# 1_BTB.net
KiCad netlist of a schematic drawn in Altium Designer
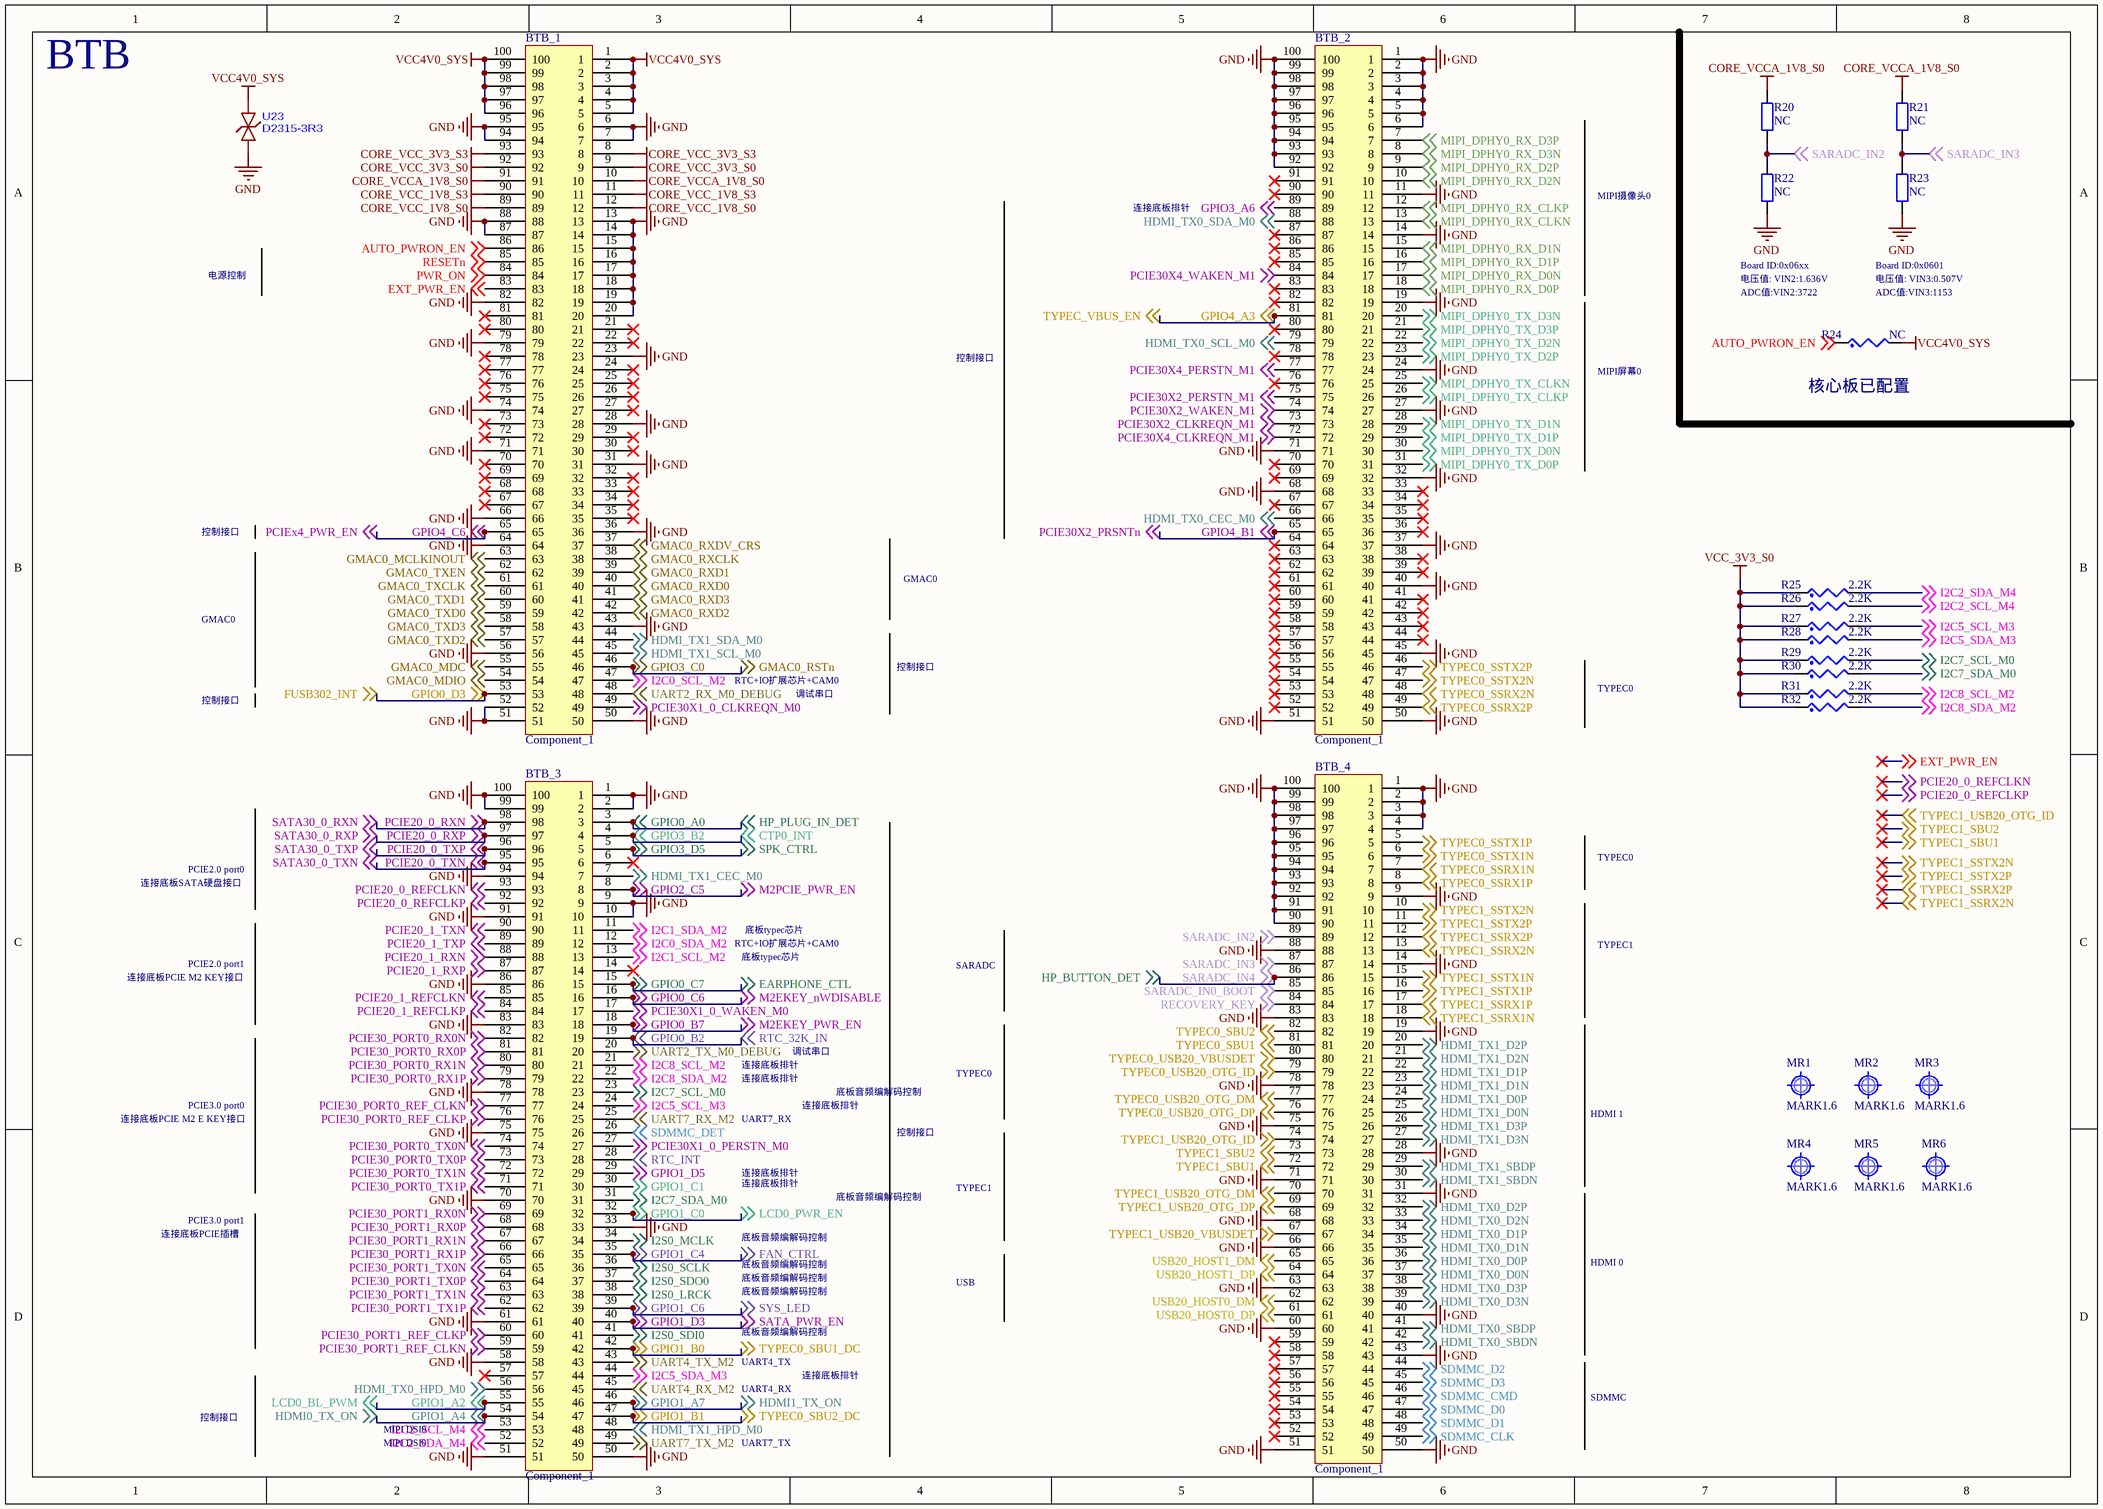
[diagram p0: 1.BTB.SchDoc]

(export (version "E")
  (design (tool "Eeschema 10.0.6"))
  (components
    (comp (ref "BTB_1")
      (value "Component_1")
      (footprint "0.PCB1:F_100PIN")
      (libsource (lib "RK3588底板") (part "Component_1"))
    )
    (comp (ref "BTB_2")
      (value "Component_1")
      (footprint "0.PCB1:F_100PIN")
      (libsource (lib "RK3588底板") (part "Component_1"))
    )
    (comp (ref "BTB_3")
      (value "Component_1")
      (footprint "0.PCB1:F_100PIN")
      (libsource (lib "RK3588底板") (part "Component_1"))
    )
    (comp (ref "BTB_4")
      (value "Component_1")
      (footprint "0.PCB1:F_100PIN")
      (libsource (lib "RK3588底板") (part "Component_1"))
    )
    (comp (ref "MR1")
      (value "MARK1.6")
      (footprint "0.PCB1:Mark 1")
      (description "光学定位点")
      (libsource (lib "RK3588底板") (part "MARK"))
    )
    (comp (ref "MR2")
      (value "MARK1.6")
      (footprint "0.PCB1:Mark 1")
      (description "光学定位点")
      (libsource (lib "RK3588底板") (part "MARK"))
    )
    (comp (ref "MR3")
      (value "MARK1.6")
      (footprint "0.PCB1:Mark 1")
      (description "光学定位点")
      (libsource (lib "RK3588底板") (part "MARK"))
    )
    (comp (ref "MR4")
      (value "MARK1.6")
      (footprint "0.PCB1:Mark 1")
      (description "光学定位点")
      (libsource (lib "RK3588底板") (part "MARK"))
    )
    (comp (ref "MR5")
      (value "MARK1.6")
      (footprint "0.PCB1:Mark 1")
      (description "光学定位点")
      (libsource (lib "RK3588底板") (part "MARK"))
    )
    (comp (ref "MR6")
      (value "MARK1.6")
      (footprint "0.PCB1:Mark 1")
      (description "光学定位点")
      (libsource (lib "RK3588底板") (part "MARK"))
    )
    (comp (ref "R20")
      (value "NC")
      (footprint "0.PCB1:R0402_L")
      (description "贴片电阻")
      (libsource (lib "RK3588底板") (part "R"))
    )
    (comp (ref "R21")
      (value "NC")
      (footprint "0.PCB1:R0402_L")
      (description "贴片电阻")
      (libsource (lib "RK3588底板") (part "R"))
    )
    (comp (ref "R22")
      (value "NC")
      (footprint "0.PCB1:R0402_L")
      (description "贴片电阻")
      (libsource (lib "RK3588底板") (part "R"))
    )
    (comp (ref "R23")
      (value "NC")
      (footprint "0.PCB1:R0402_L")
      (description "贴片电阻")
      (libsource (lib "RK3588底板") (part "R"))
    )
    (comp (ref "R24") (value "NC") (footprint "0.PCB1:R0402") (libsource (lib "RK3588底板") (part "RES")))
    (comp (ref "R25") (value "2.2K") (footprint "0.PCB1:R0402") (libsource (lib "RK3588底板") (part "RES")))
    (comp (ref "R26") (value "2.2K") (footprint "0.PCB1:R0402") (libsource (lib "RK3588底板") (part "RES")))
    (comp (ref "R27") (value "2.2K") (footprint "0.PCB1:R0402") (libsource (lib "RK3588底板") (part "RES")))
    (comp (ref "R28") (value "2.2K") (footprint "0.PCB1:R0402") (libsource (lib "RK3588底板") (part "RES")))
    (comp (ref "R29") (value "2.2K") (footprint "0.PCB1:R0402") (libsource (lib "RK3588底板") (part "RES")))
    (comp (ref "R30") (value "2.2K") (footprint "0.PCB1:R0402") (libsource (lib "RK3588底板") (part "RES")))
    (comp (ref "R31") (value "2.2K") (footprint "0.PCB1:R0402") (libsource (lib "RK3588底板") (part "RES")))
    (comp (ref "R32") (value "2.2K") (footprint "0.PCB1:R0402") (libsource (lib "RK3588底板") (part "RES")))
    (comp (ref "U23")
      (value "D2315-3R3")
      (footprint "0.PCB1:DFN1006-2L-BI")
      (libsource (lib "RK3588底板") (part "D2315-3R3"))
    )
  )
  (nets
    (net (code "1") (name "AUTO_PWRON_EN") (class "Default")
      (node (ref "BTB_1") (pin "86") (pinfunction "86_86") (pintype "passive"))
      (node (ref "R24") (pin "1") (pinfunction "1_1") (pintype "passive"))
    )
    (net (code "2") (name "CORE_VCCA_1V8_S0") (class "Default")
      (node (ref "BTB_1") (pin "10") (pinfunction "10_10") (pintype "passive"))
      (node (ref "BTB_1") (pin "91") (pinfunction "91_91") (pintype "passive"))
      (node (ref "R20") (pin "2") (pinfunction "2_2") (pintype "passive"))
      (node (ref "R21") (pin "2") (pinfunction "2_2") (pintype "passive"))
    )
    (net (code "3") (name "CORE_VCC_1V8_S0") (class "Default")
      (node (ref "BTB_1") (pin "12") (pinfunction "12_12") (pintype "passive"))
      (node (ref "BTB_1") (pin "89") (pinfunction "89_89") (pintype "passive"))
    )
    (net (code "4") (name "CORE_VCC_1V8_S3") (class "Default")
      (node (ref "BTB_1") (pin "11") (pinfunction "11_11") (pintype "passive"))
      (node (ref "BTB_1") (pin "90") (pinfunction "90_90") (pintype "passive"))
    )
    (net (code "5") (name "CORE_VCC_3V3_S0") (class "Default")
      (node (ref "BTB_1") (pin "9") (pinfunction "9_9") (pintype "passive"))
      (node (ref "BTB_1") (pin "92") (pinfunction "92_92") (pintype "passive"))
    )
    (net (code "6") (name "CORE_VCC_3V3_S3") (class "Default")
      (node (ref "BTB_1") (pin "8") (pinfunction "8_8") (pintype "passive"))
      (node (ref "BTB_1") (pin "93") (pinfunction "93_93") (pintype "passive"))
    )
    (net (code "7") (name "CTP0_INT") (class "Default")
      (node (ref "BTB_3") (pin "4") (pinfunction "4_4") (pintype "passive"))
    )
    (net (code "8") (name "EARPHONE_CTL") (class "Default")
      (node (ref "BTB_3") (pin "15") (pinfunction "15_15") (pintype "passive"))
    )
    (net (code "9") (name "EXT_PWR_EN") (class "Default")
      (node (ref "BTB_1") (pin "83") (pinfunction "83_83") (pintype "passive"))
    )
    (net (code "10") (name "FAN_CTRL") (class "Default")
      (node (ref "BTB_3") (pin "35") (pinfunction "35_35") (pintype "passive"))
    )
    (net (code "11") (name "FUSB302_INT") (class "Default")
      (node (ref "BTB_1") (pin "53") (pinfunction "53_53") (pintype "passive"))
    )
    (net (code "12") (name "GMAC0_MCLKINOUT") (class "Default")
      (node (ref "BTB_1") (pin "63") (pinfunction "63_63") (pintype "passive"))
    )
    (net (code "13") (name "GMAC0_MDC") (class "Default")
      (node (ref "BTB_1") (pin "55") (pinfunction "55_55") (pintype "passive"))
    )
    (net (code "14") (name "GMAC0_MDIO") (class "Default")
      (node (ref "BTB_1") (pin "54") (pinfunction "54_54") (pintype "passive"))
    )
    (net (code "15") (name "GMAC0_RSTn") (class "Default")
      (node (ref "BTB_1") (pin "46") (pinfunction "46_46") (pintype "passive"))
    )
    (net (code "16") (name "GMAC0_RXCLK") (class "Default")
      (node (ref "BTB_1") (pin "38") (pinfunction "38_38") (pintype "passive"))
    )
    (net (code "17") (name "GMAC0_RXD0") (class "Default")
      (node (ref "BTB_1") (pin "40") (pinfunction "40_40") (pintype "passive"))
    )
    (net (code "18") (name "GMAC0_RXD1") (class "Default")
      (node (ref "BTB_1") (pin "39") (pinfunction "39_39") (pintype "passive"))
    )
    (net (code "19") (name "GMAC0_RXD2") (class "Default")
      (node (ref "BTB_1") (pin "42") (pinfunction "42_42") (pintype "passive"))
    )
    (net (code "20") (name "GMAC0_RXD3") (class "Default")
      (node (ref "BTB_1") (pin "41") (pinfunction "41_41") (pintype "passive"))
    )
    (net (code "21") (name "GMAC0_RXDV_CRS") (class "Default")
      (node (ref "BTB_1") (pin "37") (pinfunction "37_37") (pintype "passive"))
    )
    (net (code "22") (name "GMAC0_TXCLK") (class "Default")
      (node (ref "BTB_1") (pin "61") (pinfunction "61_61") (pintype "passive"))
    )
    (net (code "23") (name "GMAC0_TXD0") (class "Default")
      (node (ref "BTB_1") (pin "59") (pinfunction "59_59") (pintype "passive"))
    )
    (net (code "24") (name "GMAC0_TXD1") (class "Default")
      (node (ref "BTB_1") (pin "60") (pinfunction "60_60") (pintype "passive"))
    )
    (net (code "25") (name "GMAC0_TXD2") (class "Default")
      (node (ref "BTB_1") (pin "57") (pinfunction "57_57") (pintype "passive"))
    )
    (net (code "26") (name "GMAC0_TXD3") (class "Default")
      (node (ref "BTB_1") (pin "58") (pinfunction "58_58") (pintype "passive"))
    )
    (net (code "27") (name "GMAC0_TXEN") (class "Default")
      (node (ref "BTB_1") (pin "62") (pinfunction "62_62") (pintype "passive"))
    )
    (net (code "28") (name "GND") (class "Default")
      (node (ref "BTB_1") (pin "13") (pinfunction "13_13") (pintype "passive"))
      (node (ref "BTB_1") (pin "14") (pinfunction "14_14") (pintype "passive"))
      (node (ref "BTB_1") (pin "15") (pinfunction "15_15") (pintype "passive"))
      (node (ref "BTB_1") (pin "16") (pinfunction "16_16") (pintype "passive"))
      (node (ref "BTB_1") (pin "17") (pinfunction "17_17") (pintype "passive"))
      (node (ref "BTB_1") (pin "18") (pinfunction "18_18") (pintype "passive"))
      (node (ref "BTB_1") (pin "19") (pinfunction "19_19") (pintype "passive"))
      (node (ref "BTB_1") (pin "20") (pinfunction "20_20") (pintype "passive"))
      (node (ref "BTB_1") (pin "23") (pinfunction "23_23") (pintype "passive"))
      (node (ref "BTB_1") (pin "28") (pinfunction "28_28") (pintype "passive"))
      (node (ref "BTB_1") (pin "31") (pinfunction "31_31") (pintype "passive"))
      (node (ref "BTB_1") (pin "36") (pinfunction "36_36") (pintype "passive"))
      (node (ref "BTB_1") (pin "43") (pinfunction "43_43") (pintype "passive"))
      (node (ref "BTB_1") (pin "50") (pinfunction "50_50") (pintype "passive"))
      (node (ref "BTB_1") (pin "51") (pinfunction "51_51") (pintype "passive"))
      (node (ref "BTB_1") (pin "52") (pinfunction "52_52") (pintype "passive"))
      (node (ref "BTB_1") (pin "56") (pinfunction "56_56") (pintype "passive"))
      (node (ref "BTB_1") (pin "6") (pinfunction "6_6") (pintype "passive"))
      (node (ref "BTB_1") (pin "64") (pinfunction "64_64") (pintype "passive"))
      (node (ref "BTB_1") (pin "66") (pinfunction "66_66") (pintype "passive"))
      (node (ref "BTB_1") (pin "7") (pinfunction "7_7") (pintype "passive"))
      (node (ref "BTB_1") (pin "71") (pinfunction "71_71") (pintype "passive"))
      (node (ref "BTB_1") (pin "74") (pinfunction "74_74") (pintype "passive"))
      (node (ref "BTB_1") (pin "79") (pinfunction "79_79") (pintype "passive"))
      (node (ref "BTB_1") (pin "82") (pinfunction "82_82") (pintype "passive"))
      (node (ref "BTB_1") (pin "87") (pinfunction "87_87") (pintype "passive"))
      (node (ref "BTB_1") (pin "88") (pinfunction "88_88") (pintype "passive"))
      (node (ref "BTB_1") (pin "94") (pinfunction "94_94") (pintype "passive"))
      (node (ref "BTB_1") (pin "95") (pinfunction "95_95") (pintype "passive"))
      (node (ref "BTB_2") (pin "1") (pinfunction "1_1") (pintype "passive"))
      (node (ref "BTB_2") (pin "100") (pinfunction "100_100") (pintype "passive"))
      (node (ref "BTB_2") (pin "11") (pinfunction "11_11") (pintype "passive"))
      (node (ref "BTB_2") (pin "14") (pinfunction "14_14") (pintype "passive"))
      (node (ref "BTB_2") (pin "19") (pinfunction "19_19") (pintype "passive"))
      (node (ref "BTB_2") (pin "2") (pinfunction "2_2") (pintype "passive"))
      (node (ref "BTB_2") (pin "24") (pinfunction "24_24") (pintype "passive"))
      (node (ref "BTB_2") (pin "27") (pinfunction "27_27") (pintype "passive"))
      (node (ref "BTB_2") (pin "3") (pinfunction "3_3") (pintype "passive"))
      (node (ref "BTB_2") (pin "32") (pinfunction "32_32") (pintype "passive"))
      (node (ref "BTB_2") (pin "37") (pinfunction "37_37") (pintype "passive"))
      (node (ref "BTB_2") (pin "4") (pinfunction "4_4") (pintype "passive"))
      (node (ref "BTB_2") (pin "40") (pinfunction "40_40") (pintype "passive"))
      (node (ref "BTB_2") (pin "45") (pinfunction "45_45") (pintype "passive"))
      (node (ref "BTB_2") (pin "5") (pinfunction "5_5") (pintype "passive"))
      (node (ref "BTB_2") (pin "50") (pinfunction "50_50") (pintype "passive"))
      (node (ref "BTB_2") (pin "51") (pinfunction "51_51") (pintype "passive"))
      (node (ref "BTB_2") (pin "6") (pinfunction "6_6") (pintype "passive"))
      (node (ref "BTB_2") (pin "68") (pinfunction "68_68") (pintype "passive"))
      (node (ref "BTB_2") (pin "71") (pinfunction "71_71") (pintype "passive"))
      (node (ref "BTB_2") (pin "92") (pinfunction "92_92") (pintype "passive"))
      (node (ref "BTB_2") (pin "93") (pinfunction "93_93") (pintype "passive"))
      (node (ref "BTB_2") (pin "94") (pinfunction "94_94") (pintype "passive"))
      (node (ref "BTB_2") (pin "95") (pinfunction "95_95") (pintype "passive"))
      (node (ref "BTB_2") (pin "96") (pinfunction "96_96") (pintype "passive"))
      (node (ref "BTB_2") (pin "97") (pinfunction "97_97") (pintype "passive"))
      (node (ref "BTB_2") (pin "98") (pinfunction "98_98") (pintype "passive"))
      (node (ref "BTB_2") (pin "99") (pinfunction "99_99") (pintype "passive"))
      (node (ref "BTB_3") (pin "1") (pinfunction "1_1") (pintype "passive"))
      (node (ref "BTB_3") (pin "10") (pinfunction "10_10") (pintype "passive"))
      (node (ref "BTB_3") (pin "100") (pinfunction "100_100") (pintype "passive"))
      (node (ref "BTB_3") (pin "2") (pinfunction "2_2") (pintype "passive"))
      (node (ref "BTB_3") (pin "33") (pinfunction "33_33") (pintype "passive"))
      (node (ref "BTB_3") (pin "50") (pinfunction "50_50") (pintype "passive"))
      (node (ref "BTB_3") (pin "51") (pinfunction "51_51") (pintype "passive"))
      (node (ref "BTB_3") (pin "58") (pinfunction "58_58") (pintype "passive"))
      (node (ref "BTB_3") (pin "61") (pinfunction "61_61") (pintype "passive"))
      (node (ref "BTB_3") (pin "70") (pinfunction "70_70") (pintype "passive"))
      (node (ref "BTB_3") (pin "75") (pinfunction "75_75") (pintype "passive"))
      (node (ref "BTB_3") (pin "78") (pinfunction "78_78") (pintype "passive"))
      (node (ref "BTB_3") (pin "83") (pinfunction "83_83") (pintype "passive"))
      (node (ref "BTB_3") (pin "86") (pinfunction "86_86") (pintype "passive"))
      (node (ref "BTB_3") (pin "9") (pinfunction "9_9") (pintype "passive"))
      (node (ref "BTB_3") (pin "91") (pinfunction "91_91") (pintype "passive"))
      (node (ref "BTB_3") (pin "94") (pinfunction "94_94") (pintype "passive"))
      (node (ref "BTB_3") (pin "99") (pinfunction "99_99") (pintype "passive"))
      (node (ref "BTB_4") (pin "1") (pinfunction "1_1") (pintype "passive"))
      (node (ref "BTB_4") (pin "100") (pinfunction "100_100") (pintype "passive"))
      (node (ref "BTB_4") (pin "14") (pinfunction "14_14") (pintype "passive"))
      (node (ref "BTB_4") (pin "19") (pinfunction "19_19") (pintype "passive"))
      (node (ref "BTB_4") (pin "2") (pinfunction "2_2") (pintype "passive"))
      (node (ref "BTB_4") (pin "28") (pinfunction "28_28") (pintype "passive"))
      (node (ref "BTB_4") (pin "3") (pinfunction "3_3") (pintype "passive"))
      (node (ref "BTB_4") (pin "31") (pinfunction "31_31") (pintype "passive"))
      (node (ref "BTB_4") (pin "4") (pinfunction "4_4") (pintype "passive"))
      (node (ref "BTB_4") (pin "40") (pinfunction "40_40") (pintype "passive"))
      (node (ref "BTB_4") (pin "43") (pinfunction "43_43") (pintype "passive"))
      (node (ref "BTB_4") (pin "50") (pinfunction "50_50") (pintype "passive"))
      (node (ref "BTB_4") (pin "51") (pinfunction "51_51") (pintype "passive"))
      (node (ref "BTB_4") (pin "60") (pinfunction "60_60") (pintype "passive"))
      (node (ref "BTB_4") (pin "63") (pinfunction "63_63") (pintype "passive"))
      (node (ref "BTB_4") (pin "66") (pinfunction "66_66") (pintype "passive"))
      (node (ref "BTB_4") (pin "68") (pinfunction "68_68") (pintype "passive"))
      (node (ref "BTB_4") (pin "71") (pinfunction "71_71") (pintype "passive"))
      (node (ref "BTB_4") (pin "75") (pinfunction "75_75") (pintype "passive"))
      (node (ref "BTB_4") (pin "78") (pinfunction "78_78") (pintype "passive"))
      (node (ref "BTB_4") (pin "83") (pinfunction "83_83") (pintype "passive"))
      (node (ref "BTB_4") (pin "88") (pinfunction "88_88") (pintype "passive"))
      (node (ref "BTB_4") (pin "9") (pinfunction "9_9") (pintype "passive"))
      (node (ref "BTB_4") (pin "90") (pinfunction "90_90") (pintype "passive"))
      (node (ref "BTB_4") (pin "91") (pinfunction "91_91") (pintype "passive"))
      (node (ref "BTB_4") (pin "92") (pinfunction "92_92") (pintype "passive"))
      (node (ref "BTB_4") (pin "93") (pinfunction "93_93") (pintype "passive"))
      (node (ref "BTB_4") (pin "94") (pinfunction "94_94") (pintype "passive"))
      (node (ref "BTB_4") (pin "95") (pinfunction "95_95") (pintype "passive"))
      (node (ref "BTB_4") (pin "96") (pinfunction "96_96") (pintype "passive"))
      (node (ref "BTB_4") (pin "97") (pinfunction "97_97") (pintype "passive"))
      (node (ref "BTB_4") (pin "98") (pinfunction "98_98") (pintype "passive"))
      (node (ref "BTB_4") (pin "99") (pinfunction "99_99") (pintype "passive"))
      (node (ref "R22") (pin "1") (pinfunction "1_1") (pintype "passive"))
      (node (ref "R23") (pin "1") (pinfunction "1_1") (pintype "passive"))
      (node (ref "U23") (pin "1") (pinfunction "1_1") (pintype "passive"))
    )
    (net (code "29") (name "GPIO0_A0") (class "Default")
      (node (ref "BTB_3") (pin "3") (pinfunction "3_3") (pintype "passive"))
    )
    (net (code "30") (name "GPIO0_B2") (class "Default")
      (node (ref "BTB_3") (pin "19") (pinfunction "19_19") (pintype "passive"))
    )
    (net (code "31") (name "GPIO0_B7") (class "Default")
      (node (ref "BTB_3") (pin "18") (pinfunction "18_18") (pintype "passive"))
    )
    (net (code "32") (name "GPIO0_C6") (class "Default")
      (node (ref "BTB_3") (pin "16") (pinfunction "16_16") (pintype "passive"))
    )
    (net (code "33") (name "GPIO1_A2") (class "Default")
      (node (ref "BTB_3") (pin "55") (pinfunction "55_55") (pintype "passive"))
    )
    (net (code "34") (name "GPIO1_A4") (class "Default")
      (node (ref "BTB_3") (pin "54") (pinfunction "54_54") (pintype "passive"))
    )
    (net (code "35") (name "GPIO1_A7") (class "Default")
      (node (ref "BTB_3") (pin "46") (pinfunction "46_46") (pintype "passive"))
    )
    (net (code "36") (name "GPIO1_B0") (class "Default")
      (node (ref "BTB_3") (pin "42") (pinfunction "42_42") (pintype "passive"))
    )
    (net (code "37") (name "GPIO1_B1") (class "Default")
      (node (ref "BTB_3") (pin "47") (pinfunction "47_47") (pintype "passive"))
    )
    (net (code "38") (name "GPIO1_C0") (class "Default")
      (node (ref "BTB_3") (pin "32") (pinfunction "32_32") (pintype "passive"))
    )
    (net (code "39") (name "GPIO1_C1") (class "Default")
      (node (ref "BTB_3") (pin "30") (pinfunction "30_30") (pintype "passive"))
    )
    (net (code "40") (name "GPIO1_C6") (class "Default")
      (node (ref "BTB_3") (pin "39") (pinfunction "39_39") (pintype "passive"))
    )
    (net (code "41") (name "GPIO1_D3") (class "Default")
      (node (ref "BTB_3") (pin "40") (pinfunction "40_40") (pintype "passive"))
    )
    (net (code "42") (name "GPIO1_D5") (class "Default")
      (node (ref "BTB_3") (pin "29") (pinfunction "29_29") (pintype "passive"))
    )
    (net (code "43") (name "GPIO2_C5") (class "Default")
      (node (ref "BTB_3") (pin "8") (pinfunction "8_8") (pintype "passive"))
    )
    (net (code "44") (name "GPIO3_A6") (class "Default")
      (node (ref "BTB_2") (pin "89") (pinfunction "89_89") (pintype "passive"))
    )
    (net (code "45") (name "GPIO3_D5") (class "Default")
      (node (ref "BTB_3") (pin "5") (pinfunction "5_5") (pintype "passive"))
    )
    (net (code "46") (name "GPIO4_A3") (class "Default")
      (node (ref "BTB_2") (pin "81") (pinfunction "81_81") (pintype "passive"))
    )
    (net (code "47") (name "GPIO4_B1") (class "Default")
      (node (ref "BTB_2") (pin "65") (pinfunction "65_65") (pintype "passive"))
    )
    (net (code "48") (name "GPIO4_C6") (class "Default")
      (node (ref "BTB_1") (pin "65") (pinfunction "65_65") (pintype "passive"))
    )
    (net (code "49") (name "HDMI_TX0_CEC_M0") (class "Default")
      (node (ref "BTB_2") (pin "66") (pinfunction "66_66") (pintype "passive"))
    )
    (net (code "50") (name "HDMI_TX0_D0N") (class "Default")
      (node (ref "BTB_4") (pin "37") (pinfunction "37_37") (pintype "passive"))
    )
    (net (code "51") (name "HDMI_TX0_D0P") (class "Default")
      (node (ref "BTB_4") (pin "36") (pinfunction "36_36") (pintype "passive"))
    )
    (net (code "52") (name "HDMI_TX0_D1N") (class "Default")
      (node (ref "BTB_4") (pin "35") (pinfunction "35_35") (pintype "passive"))
    )
    (net (code "53") (name "HDMI_TX0_D1P") (class "Default")
      (node (ref "BTB_4") (pin "34") (pinfunction "34_34") (pintype "passive"))
    )
    (net (code "54") (name "HDMI_TX0_D2N") (class "Default")
      (node (ref "BTB_4") (pin "33") (pinfunction "33_33") (pintype "passive"))
    )
    (net (code "55") (name "HDMI_TX0_D2P") (class "Default")
      (node (ref "BTB_4") (pin "32") (pinfunction "32_32") (pintype "passive"))
    )
    (net (code "56") (name "HDMI_TX0_D3N") (class "Default")
      (node (ref "BTB_4") (pin "39") (pinfunction "39_39") (pintype "passive"))
    )
    (net (code "57") (name "HDMI_TX0_D3P") (class "Default")
      (node (ref "BTB_4") (pin "38") (pinfunction "38_38") (pintype "passive"))
    )
    (net (code "58") (name "HDMI_TX0_HPD_M0") (class "Default")
      (node (ref "BTB_3") (pin "56") (pinfunction "56_56") (pintype "passive"))
    )
    (net (code "59") (name "HDMI_TX0_SBDN") (class "Default")
      (node (ref "BTB_4") (pin "42") (pinfunction "42_42") (pintype "passive"))
    )
    (net (code "60") (name "HDMI_TX0_SBDP") (class "Default")
      (node (ref "BTB_4") (pin "41") (pinfunction "41_41") (pintype "passive"))
    )
    (net (code "61") (name "HDMI_TX0_SCL_M0") (class "Default")
      (node (ref "BTB_2") (pin "79") (pinfunction "79_79") (pintype "passive"))
    )
    (net (code "62") (name "HDMI_TX0_SDA_M0") (class "Default")
      (node (ref "BTB_2") (pin "88") (pinfunction "88_88") (pintype "passive"))
    )
    (net (code "63") (name "HDMI_TX1_CEC_M0") (class "Default")
      (node (ref "BTB_3") (pin "7") (pinfunction "7_7") (pintype "passive"))
    )
    (net (code "64") (name "HDMI_TX1_D0N") (class "Default")
      (node (ref "BTB_4") (pin "25") (pinfunction "25_25") (pintype "passive"))
    )
    (net (code "65") (name "HDMI_TX1_D0P") (class "Default")
      (node (ref "BTB_4") (pin "24") (pinfunction "24_24") (pintype "passive"))
    )
    (net (code "66") (name "HDMI_TX1_D1N") (class "Default")
      (node (ref "BTB_4") (pin "23") (pinfunction "23_23") (pintype "passive"))
    )
    (net (code "67") (name "HDMI_TX1_D1P") (class "Default")
      (node (ref "BTB_4") (pin "22") (pinfunction "22_22") (pintype "passive"))
    )
    (net (code "68") (name "HDMI_TX1_D2N") (class "Default")
      (node (ref "BTB_4") (pin "21") (pinfunction "21_21") (pintype "passive"))
    )
    (net (code "69") (name "HDMI_TX1_D2P") (class "Default")
      (node (ref "BTB_4") (pin "20") (pinfunction "20_20") (pintype "passive"))
    )
    (net (code "70") (name "HDMI_TX1_D3N") (class "Default")
      (node (ref "BTB_4") (pin "27") (pinfunction "27_27") (pintype "passive"))
    )
    (net (code "71") (name "HDMI_TX1_D3P") (class "Default")
      (node (ref "BTB_4") (pin "26") (pinfunction "26_26") (pintype "passive"))
    )
    (net (code "72") (name "HDMI_TX1_HPD_M0") (class "Default")
      (node (ref "BTB_3") (pin "48") (pinfunction "48_48") (pintype "passive"))
    )
    (net (code "73") (name "HDMI_TX1_SBDN") (class "Default")
      (node (ref "BTB_4") (pin "30") (pinfunction "30_30") (pintype "passive"))
    )
    (net (code "74") (name "HDMI_TX1_SBDP") (class "Default")
      (node (ref "BTB_4") (pin "29") (pinfunction "29_29") (pintype "passive"))
    )
    (net (code "75") (name "HDMI_TX1_SCL_M0") (class "Default")
      (node (ref "BTB_1") (pin "45") (pinfunction "45_45") (pintype "passive"))
    )
    (net (code "76") (name "HDMI_TX1_SDA_M0") (class "Default")
      (node (ref "BTB_1") (pin "44") (pinfunction "44_44") (pintype "passive"))
    )
    (net (code "77") (name "HP_BUTTON_DET") (class "Default")
      (node (ref "BTB_4") (pin "86") (pinfunction "86_86") (pintype "passive"))
    )
    (net (code "78") (name "I2C0_SCL_M2") (class "Default")
      (node (ref "BTB_1") (pin "47") (pinfunction "47_47") (pintype "passive"))
    )
    (net (code "79") (name "I2C0_SDA_M2") (class "Default")
      (node (ref "BTB_3") (pin "12") (pinfunction "12_12") (pintype "passive"))
    )
    (net (code "80") (name "I2C1_SCL_M2") (class "Default")
      (node (ref "BTB_3") (pin "13") (pinfunction "13_13") (pintype "passive"))
    )
    (net (code "81") (name "I2C1_SDA_M2") (class "Default")
      (node (ref "BTB_3") (pin "11") (pinfunction "11_11") (pintype "passive"))
    )
    (net (code "82") (name "I2C2_SCL_M4") (class "Default")
      (node (ref "BTB_3") (pin "53") (pinfunction "53_53") (pintype "passive"))
      (node (ref "R26") (pin "2") (pinfunction "2_2") (pintype "passive"))
    )
    (net (code "83") (name "I2C2_SDA_M4") (class "Default")
      (node (ref "BTB_3") (pin "52") (pinfunction "52_52") (pintype "passive"))
      (node (ref "R25") (pin "2") (pinfunction "2_2") (pintype "passive"))
    )
    (net (code "84") (name "I2C5_SCL_M3") (class "Default")
      (node (ref "BTB_3") (pin "24") (pinfunction "24_24") (pintype "passive"))
      (node (ref "R27") (pin "2") (pinfunction "2_2") (pintype "passive"))
    )
    (net (code "85") (name "I2C5_SDA_M3") (class "Default")
      (node (ref "BTB_3") (pin "44") (pinfunction "44_44") (pintype "passive"))
      (node (ref "R28") (pin "2") (pinfunction "2_2") (pintype "passive"))
    )
    (net (code "86") (name "I2C7_SCL_M0") (class "Default")
      (node (ref "BTB_3") (pin "23") (pinfunction "23_23") (pintype "passive"))
      (node (ref "R29") (pin "2") (pinfunction "2_2") (pintype "passive"))
    )
    (net (code "87") (name "I2C7_SDA_M0") (class "Default")
      (node (ref "BTB_3") (pin "31") (pinfunction "31_31") (pintype "passive"))
      (node (ref "R30") (pin "2") (pinfunction "2_2") (pintype "passive"))
    )
    (net (code "88") (name "I2C8_SCL_M2") (class "Default")
      (node (ref "BTB_3") (pin "21") (pinfunction "21_21") (pintype "passive"))
      (node (ref "R31") (pin "2") (pinfunction "2_2") (pintype "passive"))
    )
    (net (code "89") (name "I2C8_SDA_M2") (class "Default")
      (node (ref "BTB_3") (pin "22") (pinfunction "22_22") (pintype "passive"))
      (node (ref "R32") (pin "2") (pinfunction "2_2") (pintype "passive"))
    )
    (net (code "90") (name "I2S0_LRCK") (class "Default")
      (node (ref "BTB_3") (pin "38") (pinfunction "38_38") (pintype "passive"))
    )
    (net (code "91") (name "I2S0_MCLK") (class "Default")
      (node (ref "BTB_3") (pin "34") (pinfunction "34_34") (pintype "passive"))
    )
    (net (code "92") (name "I2S0_SCLK") (class "Default")
      (node (ref "BTB_3") (pin "36") (pinfunction "36_36") (pintype "passive"))
    )
    (net (code "93") (name "I2S0_SDI0") (class "Default")
      (node (ref "BTB_3") (pin "41") (pinfunction "41_41") (pintype "passive"))
    )
    (net (code "94") (name "I2S0_SDO0") (class "Default")
      (node (ref "BTB_3") (pin "37") (pinfunction "37_37") (pintype "passive"))
    )
    (net (code "95") (name "MIPI_DPHY0_RX_CLKN") (class "Default")
      (node (ref "BTB_2") (pin "13") (pinfunction "13_13") (pintype "passive"))
    )
    (net (code "96") (name "MIPI_DPHY0_RX_CLKP") (class "Default")
      (node (ref "BTB_2") (pin "12") (pinfunction "12_12") (pintype "passive"))
    )
    (net (code "97") (name "MIPI_DPHY0_RX_D0N") (class "Default")
      (node (ref "BTB_2") (pin "17") (pinfunction "17_17") (pintype "passive"))
    )
    (net (code "98") (name "MIPI_DPHY0_RX_D0P") (class "Default")
      (node (ref "BTB_2") (pin "18") (pinfunction "18_18") (pintype "passive"))
    )
    (net (code "99") (name "MIPI_DPHY0_RX_D1N") (class "Default")
      (node (ref "BTB_2") (pin "15") (pinfunction "15_15") (pintype "passive"))
    )
    (net (code "100") (name "MIPI_DPHY0_RX_D1P") (class "Default")
      (node (ref "BTB_2") (pin "16") (pinfunction "16_16") (pintype "passive"))
    )
    (net (code "101") (name "MIPI_DPHY0_RX_D2N") (class "Default")
      (node (ref "BTB_2") (pin "10") (pinfunction "10_10") (pintype "passive"))
    )
    (net (code "102") (name "MIPI_DPHY0_RX_D2P") (class "Default")
      (node (ref "BTB_2") (pin "9") (pinfunction "9_9") (pintype "passive"))
    )
    (net (code "103") (name "MIPI_DPHY0_RX_D3N") (class "Default")
      (node (ref "BTB_2") (pin "8") (pinfunction "8_8") (pintype "passive"))
    )
    (net (code "104") (name "MIPI_DPHY0_RX_D3P") (class "Default")
      (node (ref "BTB_2") (pin "7") (pinfunction "7_7") (pintype "passive"))
    )
    (net (code "105") (name "MIPI_DPHY0_TX_CLKN") (class "Default")
      (node (ref "BTB_2") (pin "25") (pinfunction "25_25") (pintype "passive"))
    )
    (net (code "106") (name "MIPI_DPHY0_TX_CLKP") (class "Default")
      (node (ref "BTB_2") (pin "26") (pinfunction "26_26") (pintype "passive"))
    )
    (net (code "107") (name "MIPI_DPHY0_TX_D0N") (class "Default")
      (node (ref "BTB_2") (pin "30") (pinfunction "30_30") (pintype "passive"))
    )
    (net (code "108") (name "MIPI_DPHY0_TX_D0P") (class "Default")
      (node (ref "BTB_2") (pin "31") (pinfunction "31_31") (pintype "passive"))
    )
    (net (code "109") (name "MIPI_DPHY0_TX_D1N") (class "Default")
      (node (ref "BTB_2") (pin "28") (pinfunction "28_28") (pintype "passive"))
    )
    (net (code "110") (name "MIPI_DPHY0_TX_D1P") (class "Default")
      (node (ref "BTB_2") (pin "29") (pinfunction "29_29") (pintype "passive"))
    )
    (net (code "111") (name "MIPI_DPHY0_TX_D2N") (class "Default")
      (node (ref "BTB_2") (pin "22") (pinfunction "22_22") (pintype "passive"))
    )
    (net (code "112") (name "MIPI_DPHY0_TX_D2P") (class "Default")
      (node (ref "BTB_2") (pin "23") (pinfunction "23_23") (pintype "passive"))
    )
    (net (code "113") (name "MIPI_DPHY0_TX_D3N") (class "Default")
      (node (ref "BTB_2") (pin "20") (pinfunction "20_20") (pintype "passive"))
    )
    (net (code "114") (name "MIPI_DPHY0_TX_D3P") (class "Default")
      (node (ref "BTB_2") (pin "21") (pinfunction "21_21") (pintype "passive"))
    )
    (net (code "115") (name "PCIE20_0_REFCLKN") (class "Default")
      (node (ref "BTB_3") (pin "93") (pinfunction "93_93") (pintype "passive"))
    )
    (net (code "116") (name "PCIE20_0_REFCLKP") (class "Default")
      (node (ref "BTB_3") (pin "92") (pinfunction "92_92") (pintype "passive"))
    )
    (net (code "117") (name "PCIE20_0_RXN") (class "Default")
      (node (ref "BTB_3") (pin "98") (pinfunction "98_98") (pintype "passive"))
    )
    (net (code "118") (name "PCIE20_0_RXP") (class "Default")
      (node (ref "BTB_3") (pin "97") (pinfunction "97_97") (pintype "passive"))
    )
    (net (code "119") (name "PCIE20_0_TXN") (class "Default")
      (node (ref "BTB_3") (pin "95") (pinfunction "95_95") (pintype "passive"))
    )
    (net (code "120") (name "PCIE20_0_TXP") (class "Default")
      (node (ref "BTB_3") (pin "96") (pinfunction "96_96") (pintype "passive"))
    )
    (net (code "121") (name "PCIE20_1_REFCLKN") (class "Default")
      (node (ref "BTB_3") (pin "85") (pinfunction "85_85") (pintype "passive"))
    )
    (net (code "122") (name "PCIE20_1_REFCLKP") (class "Default")
      (node (ref "BTB_3") (pin "84") (pinfunction "84_84") (pintype "passive"))
    )
    (net (code "123") (name "PCIE20_1_RXN") (class "Default")
      (node (ref "BTB_3") (pin "88") (pinfunction "88_88") (pintype "passive"))
    )
    (net (code "124") (name "PCIE20_1_RXP") (class "Default")
      (node (ref "BTB_3") (pin "87") (pinfunction "87_87") (pintype "passive"))
    )
    (net (code "125") (name "PCIE20_1_TXN") (class "Default")
      (node (ref "BTB_3") (pin "90") (pinfunction "90_90") (pintype "passive"))
    )
    (net (code "126") (name "PCIE20_1_TXP") (class "Default")
      (node (ref "BTB_3") (pin "89") (pinfunction "89_89") (pintype "passive"))
    )
    (net (code "127") (name "PCIE30X1_0_CLKREQN_M0") (class "Default")
      (node (ref "BTB_1") (pin "49") (pinfunction "49_49") (pintype "passive"))
    )
    (net (code "128") (name "PCIE30X1_0_PERSTN_M0") (class "Default")
      (node (ref "BTB_3") (pin "27") (pinfunction "27_27") (pintype "passive"))
    )
    (net (code "129") (name "PCIE30X1_0_WAKEN_M0") (class "Default")
      (node (ref "BTB_3") (pin "17") (pinfunction "17_17") (pintype "passive"))
    )
    (net (code "130") (name "PCIE30X2_CLKREQN_M1") (class "Default")
      (node (ref "BTB_2") (pin "73") (pinfunction "73_73") (pintype "passive"))
    )
    (net (code "131") (name "PCIE30X2_PERSTN_M1") (class "Default")
      (node (ref "BTB_2") (pin "75") (pinfunction "75_75") (pintype "passive"))
    )
    (net (code "132") (name "PCIE30X2_WAKEN_M1") (class "Default")
      (node (ref "BTB_2") (pin "74") (pinfunction "74_74") (pintype "passive"))
    )
    (net (code "133") (name "PCIE30X4_CLKREQN_M1") (class "Default")
      (node (ref "BTB_2") (pin "72") (pinfunction "72_72") (pintype "passive"))
    )
    (net (code "134") (name "PCIE30X4_PERSTN_M1") (class "Default")
      (node (ref "BTB_2") (pin "77") (pinfunction "77_77") (pintype "passive"))
    )
    (net (code "135") (name "PCIE30X4_WAKEN_M1") (class "Default")
      (node (ref "BTB_2") (pin "84") (pinfunction "84_84") (pintype "passive"))
    )
    (net (code "136") (name "PCIE30_PORT0_REF_CLKN") (class "Default")
      (node (ref "BTB_3") (pin "77") (pinfunction "77_77") (pintype "passive"))
    )
    (net (code "137") (name "PCIE30_PORT0_REF_CLKP") (class "Default")
      (node (ref "BTB_3") (pin "76") (pinfunction "76_76") (pintype "passive"))
    )
    (net (code "138") (name "PCIE30_PORT0_RX0N") (class "Default")
      (node (ref "BTB_3") (pin "82") (pinfunction "82_82") (pintype "passive"))
    )
    (net (code "139") (name "PCIE30_PORT0_RX0P") (class "Default")
      (node (ref "BTB_3") (pin "81") (pinfunction "81_81") (pintype "passive"))
    )
    (net (code "140") (name "PCIE30_PORT0_RX1N") (class "Default")
      (node (ref "BTB_3") (pin "80") (pinfunction "80_80") (pintype "passive"))
    )
    (net (code "141") (name "PCIE30_PORT0_RX1P") (class "Default")
      (node (ref "BTB_3") (pin "79") (pinfunction "79_79") (pintype "passive"))
    )
    (net (code "142") (name "PCIE30_PORT0_TX0N") (class "Default")
      (node (ref "BTB_3") (pin "74") (pinfunction "74_74") (pintype "passive"))
    )
    (net (code "143") (name "PCIE30_PORT0_TX0P") (class "Default")
      (node (ref "BTB_3") (pin "73") (pinfunction "73_73") (pintype "passive"))
    )
    (net (code "144") (name "PCIE30_PORT0_TX1N") (class "Default")
      (node (ref "BTB_3") (pin "72") (pinfunction "72_72") (pintype "passive"))
    )
    (net (code "145") (name "PCIE30_PORT0_TX1P") (class "Default")
      (node (ref "BTB_3") (pin "71") (pinfunction "71_71") (pintype "passive"))
    )
    (net (code "146") (name "PCIE30_PORT1_REF_CLKN") (class "Default")
      (node (ref "BTB_3") (pin "59") (pinfunction "59_59") (pintype "passive"))
    )
    (net (code "147") (name "PCIE30_PORT1_REF_CLKP") (class "Default")
      (node (ref "BTB_3") (pin "60") (pinfunction "60_60") (pintype "passive"))
    )
    (net (code "148") (name "PCIE30_PORT1_RX0N") (class "Default")
      (node (ref "BTB_3") (pin "69") (pinfunction "69_69") (pintype "passive"))
    )
    (net (code "149") (name "PCIE30_PORT1_RX0P") (class "Default")
      (node (ref "BTB_3") (pin "68") (pinfunction "68_68") (pintype "passive"))
    )
    (net (code "150") (name "PCIE30_PORT1_RX1N") (class "Default")
      (node (ref "BTB_3") (pin "67") (pinfunction "67_67") (pintype "passive"))
    )
    (net (code "151") (name "PCIE30_PORT1_RX1P") (class "Default")
      (node (ref "BTB_3") (pin "66") (pinfunction "66_66") (pintype "passive"))
    )
    (net (code "152") (name "PCIE30_PORT1_TX0N") (class "Default")
      (node (ref "BTB_3") (pin "65") (pinfunction "65_65") (pintype "passive"))
    )
    (net (code "153") (name "PCIE30_PORT1_TX0P") (class "Default")
      (node (ref "BTB_3") (pin "64") (pinfunction "64_64") (pintype "passive"))
    )
    (net (code "154") (name "PCIE30_PORT1_TX1N") (class "Default")
      (node (ref "BTB_3") (pin "63") (pinfunction "63_63") (pintype "passive"))
    )
    (net (code "155") (name "PCIE30_PORT1_TX1P") (class "Default")
      (node (ref "BTB_3") (pin "62") (pinfunction "62_62") (pintype "passive"))
    )
    (net (code "156") (name "PWR_ON") (class "Default")
      (node (ref "BTB_1") (pin "84") (pinfunction "84_84") (pintype "passive"))
    )
    (net (code "157") (name "RECOVERY_KEY") (class "Default")
      (node (ref "BTB_4") (pin "84") (pinfunction "84_84") (pintype "passive"))
    )
    (net (code "158") (name "RESETn") (class "Default")
      (node (ref "BTB_1") (pin "85") (pinfunction "85_85") (pintype "passive"))
    )
    (net (code "159") (name "RTC_INT") (class "Default")
      (node (ref "BTB_3") (pin "28") (pinfunction "28_28") (pintype "passive"))
    )
    (net (code "160") (name "SARADC_IN0_BOOT") (class "Default")
      (node (ref "BTB_4") (pin "85") (pinfunction "85_85") (pintype "passive"))
    )
    (net (code "161") (name "SARADC_IN2") (class "Default")
      (node (ref "BTB_4") (pin "89") (pinfunction "89_89") (pintype "passive"))
      (node (ref "R20") (pin "1") (pinfunction "1_1") (pintype "passive"))
      (node (ref "R22") (pin "2") (pinfunction "2_2") (pintype "passive"))
    )
    (net (code "162") (name "SARADC_IN3") (class "Default")
      (node (ref "BTB_4") (pin "87") (pinfunction "87_87") (pintype "passive"))
      (node (ref "R21") (pin "1") (pinfunction "1_1") (pintype "passive"))
      (node (ref "R23") (pin "2") (pinfunction "2_2") (pintype "passive"))
    )
    (net (code "163") (name "SDMMC_CLK") (class "Default")
      (node (ref "BTB_4") (pin "49") (pinfunction "49_49") (pintype "passive"))
    )
    (net (code "164") (name "SDMMC_CMD") (class "Default")
      (node (ref "BTB_4") (pin "46") (pinfunction "46_46") (pintype "passive"))
    )
    (net (code "165") (name "SDMMC_D0") (class "Default")
      (node (ref "BTB_4") (pin "47") (pinfunction "47_47") (pintype "passive"))
    )
    (net (code "166") (name "SDMMC_D1") (class "Default")
      (node (ref "BTB_4") (pin "48") (pinfunction "48_48") (pintype "passive"))
    )
    (net (code "167") (name "SDMMC_D2") (class "Default")
      (node (ref "BTB_4") (pin "44") (pinfunction "44_44") (pintype "passive"))
    )
    (net (code "168") (name "SDMMC_D3") (class "Default")
      (node (ref "BTB_4") (pin "45") (pinfunction "45_45") (pintype "passive"))
    )
    (net (code "169") (name "SDMMC_DET") (class "Default")
      (node (ref "BTB_3") (pin "26") (pinfunction "26_26") (pintype "passive"))
    )
    (net (code "170") (name "TYPEC0_SBU1") (class "Default")
      (node (ref "BTB_4") (pin "81") (pinfunction "81_81") (pintype "passive"))
    )
    (net (code "171") (name "TYPEC0_SBU2") (class "Default")
      (node (ref "BTB_4") (pin "82") (pinfunction "82_82") (pintype "passive"))
    )
    (net (code "172") (name "TYPEC0_SSRX1N") (class "Default")
      (node (ref "BTB_4") (pin "7") (pinfunction "7_7") (pintype "passive"))
    )
    (net (code "173") (name "TYPEC0_SSRX1P") (class "Default")
      (node (ref "BTB_4") (pin "8") (pinfunction "8_8") (pintype "passive"))
    )
    (net (code "174") (name "TYPEC0_SSRX2N") (class "Default")
      (node (ref "BTB_2") (pin "48") (pinfunction "48_48") (pintype "passive"))
    )
    (net (code "175") (name "TYPEC0_SSRX2P") (class "Default")
      (node (ref "BTB_2") (pin "49") (pinfunction "49_49") (pintype "passive"))
    )
    (net (code "176") (name "TYPEC0_SSTX1N") (class "Default")
      (node (ref "BTB_4") (pin "6") (pinfunction "6_6") (pintype "passive"))
    )
    (net (code "177") (name "TYPEC0_SSTX1P") (class "Default")
      (node (ref "BTB_4") (pin "5") (pinfunction "5_5") (pintype "passive"))
    )
    (net (code "178") (name "TYPEC0_SSTX2N") (class "Default")
      (node (ref "BTB_2") (pin "47") (pinfunction "47_47") (pintype "passive"))
    )
    (net (code "179") (name "TYPEC0_SSTX2P") (class "Default")
      (node (ref "BTB_2") (pin "46") (pinfunction "46_46") (pintype "passive"))
    )
    (net (code "180") (name "TYPEC0_USB20_OTG_DM") (class "Default")
      (node (ref "BTB_4") (pin "77") (pinfunction "77_77") (pintype "passive"))
    )
    (net (code "181") (name "TYPEC0_USB20_OTG_DP") (class "Default")
      (node (ref "BTB_4") (pin "76") (pinfunction "76_76") (pintype "passive"))
    )
    (net (code "182") (name "TYPEC0_USB20_OTG_ID") (class "Default")
      (node (ref "BTB_4") (pin "79") (pinfunction "79_79") (pintype "passive"))
    )
    (net (code "183") (name "TYPEC0_USB20_VBUSDET") (class "Default")
      (node (ref "BTB_4") (pin "80") (pinfunction "80_80") (pintype "passive"))
    )
    (net (code "184") (name "TYPEC1_SBU1") (class "Default")
      (node (ref "BTB_4") (pin "72") (pinfunction "72_72") (pintype "passive"))
    )
    (net (code "185") (name "TYPEC1_SBU2") (class "Default")
      (node (ref "BTB_4") (pin "73") (pinfunction "73_73") (pintype "passive"))
    )
    (net (code "186") (name "TYPEC1_SSRX1N") (class "Default")
      (node (ref "BTB_4") (pin "18") (pinfunction "18_18") (pintype "passive"))
    )
    (net (code "187") (name "TYPEC1_SSRX1P") (class "Default")
      (node (ref "BTB_4") (pin "17") (pinfunction "17_17") (pintype "passive"))
    )
    (net (code "188") (name "TYPEC1_SSRX2N") (class "Default")
      (node (ref "BTB_4") (pin "13") (pinfunction "13_13") (pintype "passive"))
    )
    (net (code "189") (name "TYPEC1_SSRX2P") (class "Default")
      (node (ref "BTB_4") (pin "12") (pinfunction "12_12") (pintype "passive"))
    )
    (net (code "190") (name "TYPEC1_SSTX1N") (class "Default")
      (node (ref "BTB_4") (pin "15") (pinfunction "15_15") (pintype "passive"))
    )
    (net (code "191") (name "TYPEC1_SSTX1P") (class "Default")
      (node (ref "BTB_4") (pin "16") (pinfunction "16_16") (pintype "passive"))
    )
    (net (code "192") (name "TYPEC1_SSTX2N") (class "Default")
      (node (ref "BTB_4") (pin "10") (pinfunction "10_10") (pintype "passive"))
    )
    (net (code "193") (name "TYPEC1_SSTX2P") (class "Default")
      (node (ref "BTB_4") (pin "11") (pinfunction "11_11") (pintype "passive"))
    )
    (net (code "194") (name "TYPEC1_USB20_OTG_DM") (class "Default")
      (node (ref "BTB_4") (pin "70") (pinfunction "70_70") (pintype "passive"))
    )
    (net (code "195") (name "TYPEC1_USB20_OTG_DP") (class "Default")
      (node (ref "BTB_4") (pin "69") (pinfunction "69_69") (pintype "passive"))
    )
    (net (code "196") (name "TYPEC1_USB20_OTG_ID") (class "Default")
      (node (ref "BTB_4") (pin "74") (pinfunction "74_74") (pintype "passive"))
    )
    (net (code "197") (name "TYPEC1_USB20_VBUSDET") (class "Default")
      (node (ref "BTB_4") (pin "67") (pinfunction "67_67") (pintype "passive"))
    )
    (net (code "198") (name "UART2_RX_M0_DEBUG") (class "Default")
      (node (ref "BTB_1") (pin "48") (pinfunction "48_48") (pintype "passive"))
    )
    (net (code "199") (name "UART2_TX_M0_DEBUG") (class "Default")
      (node (ref "BTB_3") (pin "20") (pinfunction "20_20") (pintype "passive"))
    )
    (net (code "200") (name "UART4_RX_M2") (class "Default")
      (node (ref "BTB_3") (pin "45") (pinfunction "45_45") (pintype "passive"))
    )
    (net (code "201") (name "UART4_TX_M2") (class "Default")
      (node (ref "BTB_3") (pin "43") (pinfunction "43_43") (pintype "passive"))
    )
    (net (code "202") (name "UART7_RX_M2") (class "Default")
      (node (ref "BTB_3") (pin "25") (pinfunction "25_25") (pintype "passive"))
    )
    (net (code "203") (name "UART7_TX_M2") (class "Default")
      (node (ref "BTB_3") (pin "49") (pinfunction "49_49") (pintype "passive"))
    )
    (net (code "204") (name "USB20_HOST0_DM") (class "Default")
      (node (ref "BTB_4") (pin "62") (pinfunction "62_62") (pintype "passive"))
    )
    (net (code "205") (name "USB20_HOST0_DP") (class "Default")
      (node (ref "BTB_4") (pin "61") (pinfunction "61_61") (pintype "passive"))
    )
    (net (code "206") (name "USB20_HOST1_DM") (class "Default")
      (node (ref "BTB_4") (pin "65") (pinfunction "65_65") (pintype "passive"))
    )
    (net (code "207") (name "USB20_HOST1_DP") (class "Default")
      (node (ref "BTB_4") (pin "64") (pinfunction "64_64") (pintype "passive"))
    )
    (net (code "208") (name "VCC4V0_SYS") (class "Default")
      (node (ref "BTB_1") (pin "1") (pinfunction "1_1") (pintype "passive"))
      (node (ref "BTB_1") (pin "100") (pinfunction "100_100") (pintype "passive"))
      (node (ref "BTB_1") (pin "2") (pinfunction "2_2") (pintype "passive"))
      (node (ref "BTB_1") (pin "3") (pinfunction "3_3") (pintype "passive"))
      (node (ref "BTB_1") (pin "4") (pinfunction "4_4") (pintype "passive"))
      (node (ref "BTB_1") (pin "5") (pinfunction "5_5") (pintype "passive"))
      (node (ref "BTB_1") (pin "96") (pinfunction "96_96") (pintype "passive"))
      (node (ref "BTB_1") (pin "97") (pinfunction "97_97") (pintype "passive"))
      (node (ref "BTB_1") (pin "98") (pinfunction "98_98") (pintype "passive"))
      (node (ref "BTB_1") (pin "99") (pinfunction "99_99") (pintype "passive"))
      (node (ref "R24") (pin "2") (pinfunction "2_2") (pintype "passive"))
      (node (ref "U23") (pin "2") (pinfunction "2_2") (pintype "passive"))
    )
    (net (code "209") (name "VCC_3V3_S0") (class "Default")
      (node (ref "R25") (pin "1") (pinfunction "1_1") (pintype "passive"))
      (node (ref "R26") (pin "1") (pinfunction "1_1") (pintype "passive"))
      (node (ref "R27") (pin "1") (pinfunction "1_1") (pintype "passive"))
      (node (ref "R28") (pin "1") (pinfunction "1_1") (pintype "passive"))
      (node (ref "R29") (pin "1") (pinfunction "1_1") (pintype "passive"))
      (node (ref "R30") (pin "1") (pinfunction "1_1") (pintype "passive"))
      (node (ref "R31") (pin "1") (pinfunction "1_1") (pintype "passive"))
      (node (ref "R32") (pin "1") (pinfunction "1_1") (pintype "passive"))
    )
    (net (code "210") (name "unconnected-(BTB_1-Pad21)") (class "Default")
      (node (ref "BTB_1") (pin "21") (pinfunction "21_21") (pintype "passive+no_connect"))
    )
    (net (code "211") (name "unconnected-(BTB_1-Pad22)") (class "Default")
      (node (ref "BTB_1") (pin "22") (pinfunction "22_22") (pintype "passive+no_connect"))
    )
    (net (code "212") (name "unconnected-(BTB_1-Pad24)") (class "Default")
      (node (ref "BTB_1") (pin "24") (pinfunction "24_24") (pintype "passive+no_connect"))
    )
    (net (code "213") (name "unconnected-(BTB_1-Pad25)") (class "Default")
      (node (ref "BTB_1") (pin "25") (pinfunction "25_25") (pintype "passive+no_connect"))
    )
    (net (code "214") (name "unconnected-(BTB_1-Pad26)") (class "Default")
      (node (ref "BTB_1") (pin "26") (pinfunction "26_26") (pintype "passive+no_connect"))
    )
    (net (code "215") (name "unconnected-(BTB_1-Pad27)") (class "Default")
      (node (ref "BTB_1") (pin "27") (pinfunction "27_27") (pintype "passive+no_connect"))
    )
    (net (code "216") (name "unconnected-(BTB_1-Pad29)") (class "Default")
      (node (ref "BTB_1") (pin "29") (pinfunction "29_29") (pintype "passive+no_connect"))
    )
    (net (code "217") (name "unconnected-(BTB_1-Pad30)") (class "Default")
      (node (ref "BTB_1") (pin "30") (pinfunction "30_30") (pintype "passive+no_connect"))
    )
    (net (code "218") (name "unconnected-(BTB_1-Pad32)") (class "Default")
      (node (ref "BTB_1") (pin "32") (pinfunction "32_32") (pintype "passive+no_connect"))
    )
    (net (code "219") (name "unconnected-(BTB_1-Pad33)") (class "Default")
      (node (ref "BTB_1") (pin "33") (pinfunction "33_33") (pintype "passive+no_connect"))
    )
    (net (code "220") (name "unconnected-(BTB_1-Pad34)") (class "Default")
      (node (ref "BTB_1") (pin "34") (pinfunction "34_34") (pintype "passive+no_connect"))
    )
    (net (code "221") (name "unconnected-(BTB_1-Pad35)") (class "Default")
      (node (ref "BTB_1") (pin "35") (pinfunction "35_35") (pintype "passive+no_connect"))
    )
    (net (code "222") (name "unconnected-(BTB_1-Pad67)") (class "Default")
      (node (ref "BTB_1") (pin "67") (pinfunction "67_67") (pintype "passive+no_connect"))
    )
    (net (code "223") (name "unconnected-(BTB_1-Pad68)") (class "Default")
      (node (ref "BTB_1") (pin "68") (pinfunction "68_68") (pintype "passive+no_connect"))
    )
    (net (code "224") (name "unconnected-(BTB_1-Pad69)") (class "Default")
      (node (ref "BTB_1") (pin "69") (pinfunction "69_69") (pintype "passive+no_connect"))
    )
    (net (code "225") (name "unconnected-(BTB_1-Pad70)") (class "Default")
      (node (ref "BTB_1") (pin "70") (pinfunction "70_70") (pintype "passive+no_connect"))
    )
    (net (code "226") (name "unconnected-(BTB_1-Pad72)") (class "Default")
      (node (ref "BTB_1") (pin "72") (pinfunction "72_72") (pintype "passive+no_connect"))
    )
    (net (code "227") (name "unconnected-(BTB_1-Pad73)") (class "Default")
      (node (ref "BTB_1") (pin "73") (pinfunction "73_73") (pintype "passive+no_connect"))
    )
    (net (code "228") (name "unconnected-(BTB_1-Pad75)") (class "Default")
      (node (ref "BTB_1") (pin "75") (pinfunction "75_75") (pintype "passive+no_connect"))
    )
    (net (code "229") (name "unconnected-(BTB_1-Pad76)") (class "Default")
      (node (ref "BTB_1") (pin "76") (pinfunction "76_76") (pintype "passive+no_connect"))
    )
    (net (code "230") (name "unconnected-(BTB_1-Pad77)") (class "Default")
      (node (ref "BTB_1") (pin "77") (pinfunction "77_77") (pintype "passive+no_connect"))
    )
    (net (code "231") (name "unconnected-(BTB_1-Pad78)") (class "Default")
      (node (ref "BTB_1") (pin "78") (pinfunction "78_78") (pintype "passive+no_connect"))
    )
    (net (code "232") (name "unconnected-(BTB_1-Pad80)") (class "Default")
      (node (ref "BTB_1") (pin "80") (pinfunction "80_80") (pintype "passive+no_connect"))
    )
    (net (code "233") (name "unconnected-(BTB_1-Pad81)") (class "Default")
      (node (ref "BTB_1") (pin "81") (pinfunction "81_81") (pintype "passive+no_connect"))
    )
    (net (code "234") (name "unconnected-(BTB_2-Pad33)") (class "Default")
      (node (ref "BTB_2") (pin "33") (pinfunction "33_33") (pintype "passive+no_connect"))
    )
    (net (code "235") (name "unconnected-(BTB_2-Pad34)") (class "Default")
      (node (ref "BTB_2") (pin "34") (pinfunction "34_34") (pintype "passive+no_connect"))
    )
    (net (code "236") (name "unconnected-(BTB_2-Pad35)") (class "Default")
      (node (ref "BTB_2") (pin "35") (pinfunction "35_35") (pintype "passive+no_connect"))
    )
    (net (code "237") (name "unconnected-(BTB_2-Pad36)") (class "Default")
      (node (ref "BTB_2") (pin "36") (pinfunction "36_36") (pintype "passive+no_connect"))
    )
    (net (code "238") (name "unconnected-(BTB_2-Pad38)") (class "Default")
      (node (ref "BTB_2") (pin "38") (pinfunction "38_38") (pintype "passive+no_connect"))
    )
    (net (code "239") (name "unconnected-(BTB_2-Pad39)") (class "Default")
      (node (ref "BTB_2") (pin "39") (pinfunction "39_39") (pintype "passive+no_connect"))
    )
    (net (code "240") (name "unconnected-(BTB_2-Pad41)") (class "Default")
      (node (ref "BTB_2") (pin "41") (pinfunction "41_41") (pintype "passive+no_connect"))
    )
    (net (code "241") (name "unconnected-(BTB_2-Pad42)") (class "Default")
      (node (ref "BTB_2") (pin "42") (pinfunction "42_42") (pintype "passive+no_connect"))
    )
    (net (code "242") (name "unconnected-(BTB_2-Pad43)") (class "Default")
      (node (ref "BTB_2") (pin "43") (pinfunction "43_43") (pintype "passive+no_connect"))
    )
    (net (code "243") (name "unconnected-(BTB_2-Pad44)") (class "Default")
      (node (ref "BTB_2") (pin "44") (pinfunction "44_44") (pintype "passive+no_connect"))
    )
    (net (code "244") (name "unconnected-(BTB_2-Pad52)") (class "Default")
      (node (ref "BTB_2") (pin "52") (pinfunction "52_52") (pintype "passive+no_connect"))
    )
    (net (code "245") (name "unconnected-(BTB_2-Pad53)") (class "Default")
      (node (ref "BTB_2") (pin "53") (pinfunction "53_53") (pintype "passive+no_connect"))
    )
    (net (code "246") (name "unconnected-(BTB_2-Pad54)") (class "Default")
      (node (ref "BTB_2") (pin "54") (pinfunction "54_54") (pintype "passive+no_connect"))
    )
    (net (code "247") (name "unconnected-(BTB_2-Pad55)") (class "Default")
      (node (ref "BTB_2") (pin "55") (pinfunction "55_55") (pintype "passive+no_connect"))
    )
    (net (code "248") (name "unconnected-(BTB_2-Pad56)") (class "Default")
      (node (ref "BTB_2") (pin "56") (pinfunction "56_56") (pintype "passive+no_connect"))
    )
    (net (code "249") (name "unconnected-(BTB_2-Pad57)") (class "Default")
      (node (ref "BTB_2") (pin "57") (pinfunction "57_57") (pintype "passive+no_connect"))
    )
    (net (code "250") (name "unconnected-(BTB_2-Pad58)") (class "Default")
      (node (ref "BTB_2") (pin "58") (pinfunction "58_58") (pintype "passive+no_connect"))
    )
    (net (code "251") (name "unconnected-(BTB_2-Pad59)") (class "Default")
      (node (ref "BTB_2") (pin "59") (pinfunction "59_59") (pintype "passive+no_connect"))
    )
    (net (code "252") (name "unconnected-(BTB_2-Pad60)") (class "Default")
      (node (ref "BTB_2") (pin "60") (pinfunction "60_60") (pintype "passive+no_connect"))
    )
    (net (code "253") (name "unconnected-(BTB_2-Pad61)") (class "Default")
      (node (ref "BTB_2") (pin "61") (pinfunction "61_61") (pintype "passive+no_connect"))
    )
    (net (code "254") (name "unconnected-(BTB_2-Pad62)") (class "Default")
      (node (ref "BTB_2") (pin "62") (pinfunction "62_62") (pintype "passive+no_connect"))
    )
    (net (code "255") (name "unconnected-(BTB_2-Pad63)") (class "Default")
      (node (ref "BTB_2") (pin "63") (pinfunction "63_63") (pintype "passive+no_connect"))
    )
    (net (code "256") (name "unconnected-(BTB_2-Pad64)") (class "Default")
      (node (ref "BTB_2") (pin "64") (pinfunction "64_64") (pintype "passive+no_connect"))
    )
    (net (code "257") (name "unconnected-(BTB_2-Pad67)") (class "Default")
      (node (ref "BTB_2") (pin "67") (pinfunction "67_67") (pintype "passive+no_connect"))
    )
    (net (code "258") (name "unconnected-(BTB_2-Pad69)") (class "Default")
      (node (ref "BTB_2") (pin "69") (pinfunction "69_69") (pintype "passive+no_connect"))
    )
    (net (code "259") (name "unconnected-(BTB_2-Pad70)") (class "Default")
      (node (ref "BTB_2") (pin "70") (pinfunction "70_70") (pintype "passive+no_connect"))
    )
    (net (code "260") (name "unconnected-(BTB_2-Pad76)") (class "Default")
      (node (ref "BTB_2") (pin "76") (pinfunction "76_76") (pintype "passive+no_connect"))
    )
    (net (code "261") (name "unconnected-(BTB_2-Pad78)") (class "Default")
      (node (ref "BTB_2") (pin "78") (pinfunction "78_78") (pintype "passive+no_connect"))
    )
    (net (code "262") (name "unconnected-(BTB_2-Pad80)") (class "Default")
      (node (ref "BTB_2") (pin "80") (pinfunction "80_80") (pintype "passive+no_connect"))
    )
    (net (code "263") (name "unconnected-(BTB_2-Pad82)") (class "Default")
      (node (ref "BTB_2") (pin "82") (pinfunction "82_82") (pintype "passive+no_connect"))
    )
    (net (code "264") (name "unconnected-(BTB_2-Pad83)") (class "Default")
      (node (ref "BTB_2") (pin "83") (pinfunction "83_83") (pintype "passive+no_connect"))
    )
    (net (code "265") (name "unconnected-(BTB_2-Pad85)") (class "Default")
      (node (ref "BTB_2") (pin "85") (pinfunction "85_85") (pintype "passive+no_connect"))
    )
    (net (code "266") (name "unconnected-(BTB_2-Pad86)") (class "Default")
      (node (ref "BTB_2") (pin "86") (pinfunction "86_86") (pintype "passive+no_connect"))
    )
    (net (code "267") (name "unconnected-(BTB_2-Pad87)") (class "Default")
      (node (ref "BTB_2") (pin "87") (pinfunction "87_87") (pintype "passive+no_connect"))
    )
    (net (code "268") (name "unconnected-(BTB_2-Pad90)") (class "Default")
      (node (ref "BTB_2") (pin "90") (pinfunction "90_90") (pintype "passive+no_connect"))
    )
    (net (code "269") (name "unconnected-(BTB_2-Pad91)") (class "Default")
      (node (ref "BTB_2") (pin "91") (pinfunction "91_91") (pintype "passive+no_connect"))
    )
    (net (code "270") (name "unconnected-(BTB_3-Pad6)") (class "Default")
      (node (ref "BTB_3") (pin "6") (pinfunction "6_6") (pintype "passive+no_connect"))
    )
    (net (code "271") (name "unconnected-(BTB_3-Pad14)") (class "Default")
      (node (ref "BTB_3") (pin "14") (pinfunction "14_14") (pintype "passive+no_connect"))
    )
    (net (code "272") (name "unconnected-(BTB_3-Pad57)") (class "Default")
      (node (ref "BTB_3") (pin "57") (pinfunction "57_57") (pintype "passive+no_connect"))
    )
    (net (code "273") (name "unconnected-(BTB_4-Pad52)") (class "Default")
      (node (ref "BTB_4") (pin "52") (pinfunction "52_52") (pintype "passive+no_connect"))
    )
    (net (code "274") (name "unconnected-(BTB_4-Pad53)") (class "Default")
      (node (ref "BTB_4") (pin "53") (pinfunction "53_53") (pintype "passive+no_connect"))
    )
    (net (code "275") (name "unconnected-(BTB_4-Pad54)") (class "Default")
      (node (ref "BTB_4") (pin "54") (pinfunction "54_54") (pintype "passive+no_connect"))
    )
    (net (code "276") (name "unconnected-(BTB_4-Pad55)") (class "Default")
      (node (ref "BTB_4") (pin "55") (pinfunction "55_55") (pintype "passive+no_connect"))
    )
    (net (code "277") (name "unconnected-(BTB_4-Pad56)") (class "Default")
      (node (ref "BTB_4") (pin "56") (pinfunction "56_56") (pintype "passive+no_connect"))
    )
    (net (code "278") (name "unconnected-(BTB_4-Pad57)") (class "Default")
      (node (ref "BTB_4") (pin "57") (pinfunction "57_57") (pintype "passive+no_connect"))
    )
    (net (code "279") (name "unconnected-(BTB_4-Pad58)") (class "Default")
      (node (ref "BTB_4") (pin "58") (pinfunction "58_58") (pintype "passive+no_connect"))
    )
    (net (code "280") (name "unconnected-(BTB_4-Pad59)") (class "Default")
      (node (ref "BTB_4") (pin "59") (pinfunction "59_59") (pintype "passive+no_connect"))
    )
  )
)
